# 30ApowerDist.net
KiCad netlist of a schematic drawn in EAGLE
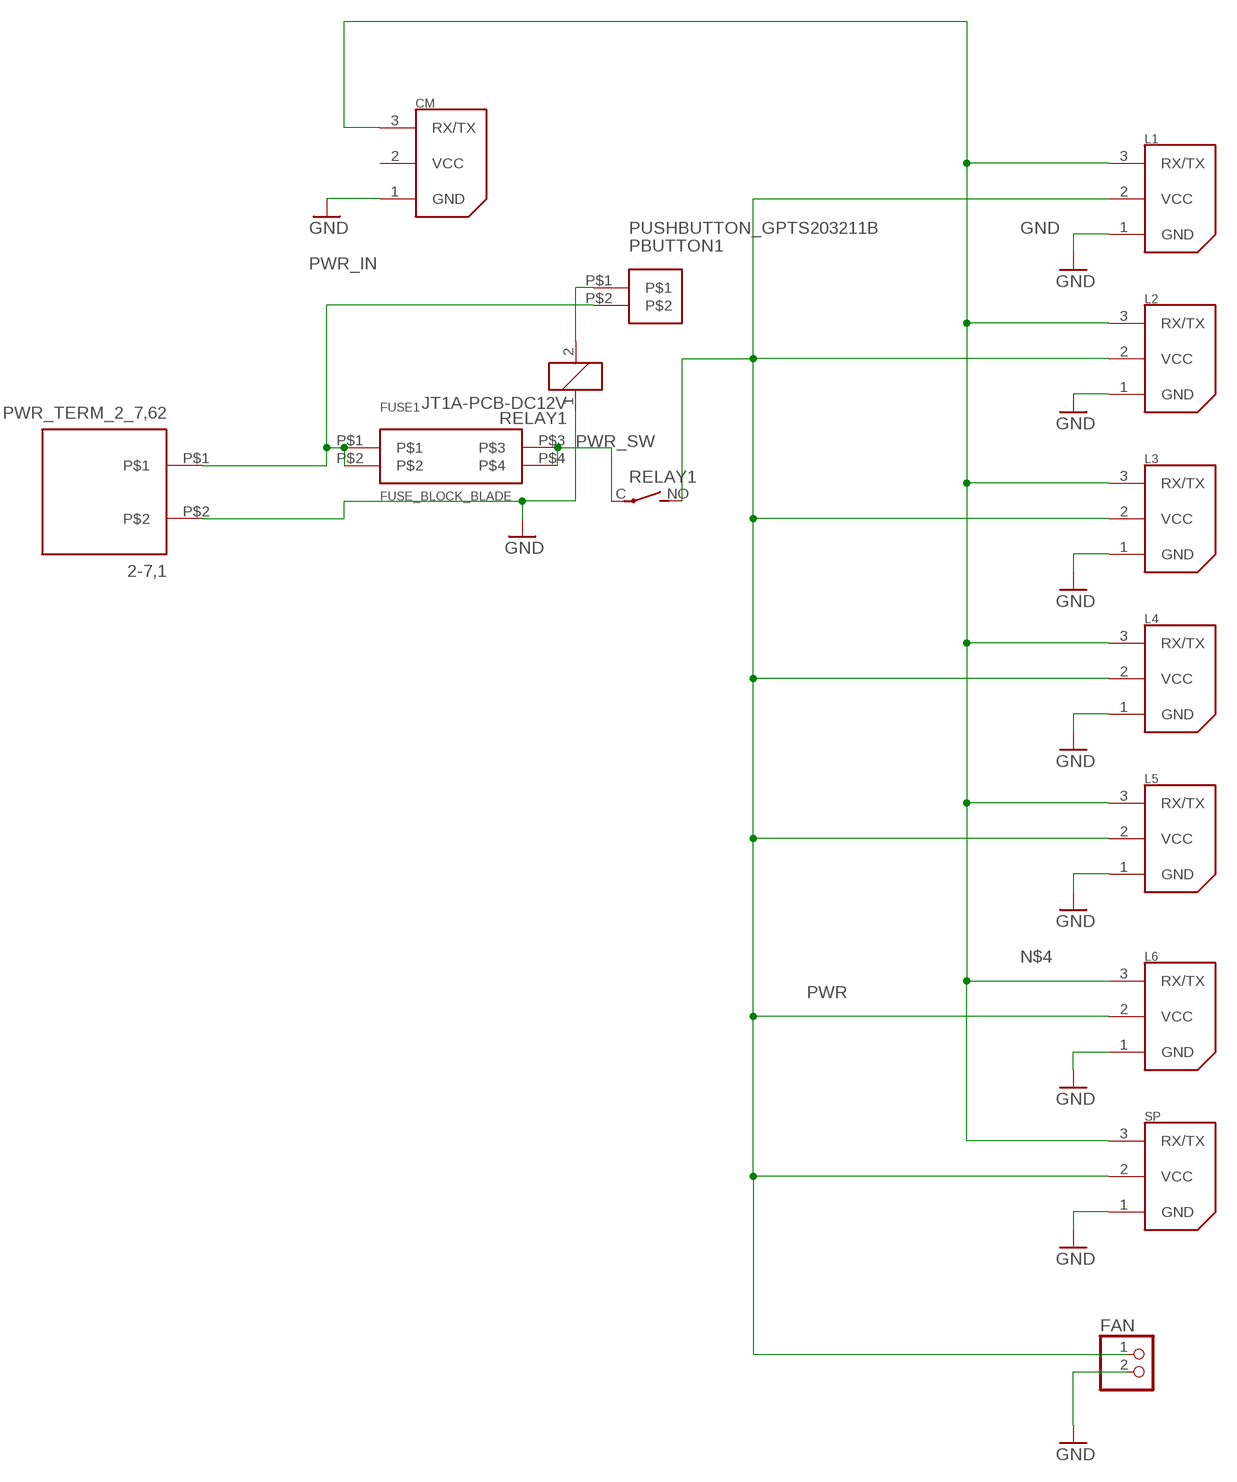
[diagram p0: schematic, sheet 1]

(export (version "E")
  (design (tool "Eeschema 10.0.6"))
  (components
    (comp (ref "2-7,1")
      (value "PWR_TERM_2_7,62")
      (footprint "eagle-import:PWR_TERM_2_7,62")
      (libsource (lib "eagle-import") (part "PWR_TERM_2_7,62"))
    )
    (comp (ref "CM")
      (value "22-03-5035")
      (footprint "eagle-import:5267-3")
      (libsource (lib "eagle-import") (part "22-03-5035"))
    )
    (comp (ref "FAN")
      (value "PINHD-1X2")
      (footprint "eagle-import:1X02")
      (libsource (lib "eagle-import") (part "PINHD-1X2"))
    )
    (comp (ref "FUSE1")
      (value "FUSE_BLOCK_BLADE")
      (footprint "eagle-import:FUSE_BLOCK_BLADE")
      (libsource (lib "eagle-import") (part "FUSE_BLOCK_BLADE"))
    )
    (comp (ref "L1")
      (value "22-03-5035")
      (footprint "eagle-import:5267-3")
      (libsource (lib "eagle-import") (part "22-03-5035"))
    )
    (comp (ref "L2")
      (value "22-03-5035")
      (footprint "eagle-import:5267-3")
      (libsource (lib "eagle-import") (part "22-03-5035"))
    )
    (comp (ref "L3")
      (value "22-03-5035")
      (footprint "eagle-import:5267-3")
      (libsource (lib "eagle-import") (part "22-03-5035"))
    )
    (comp (ref "L4")
      (value "22-03-5035")
      (footprint "eagle-import:5267-3")
      (libsource (lib "eagle-import") (part "22-03-5035"))
    )
    (comp (ref "L5")
      (value "22-03-5035")
      (footprint "eagle-import:5267-3")
      (libsource (lib "eagle-import") (part "22-03-5035"))
    )
    (comp (ref "L6")
      (value "22-03-5035")
      (footprint "eagle-import:5267-3")
      (libsource (lib "eagle-import") (part "22-03-5035"))
    )
    (comp (ref "PBUTTON1")
      (value "PUSHBUTTON_GPTS203211B")
      (footprint "eagle-import:PUSHBUTTON_GPTS203211B")
      (libsource (lib "eagle-import") (part "PUSHBUTTON_GPTS203211B"))
    )
    (comp (ref "RELAY1")
      (value "JT1A-PCB-DC12V")
      (footprint "eagle-import:JT1A-PCB")
      (libsource (lib "eagle-import") (part "JT1A?--PCBDC12V"))
    )
    (comp (ref "SP")
      (value "22-03-5035")
      (footprint "eagle-import:5267-3")
      (libsource (lib "eagle-import") (part "22-03-5035"))
    )
  )
  (nets
    (net (code "1") (name "/N$4") (class "Default")
      (node (ref "CM") (pin "3") (pinfunction "RX/TX_3") (pintype "bidirectional"))
      (node (ref "L1") (pin "3") (pinfunction "RX/TX_3") (pintype "bidirectional"))
      (node (ref "L2") (pin "3") (pinfunction "RX/TX_3") (pintype "bidirectional"))
      (node (ref "L3") (pin "3") (pinfunction "RX/TX_3") (pintype "bidirectional"))
      (node (ref "L4") (pin "3") (pinfunction "RX/TX_3") (pintype "bidirectional"))
      (node (ref "L5") (pin "3") (pinfunction "RX/TX_3") (pintype "bidirectional"))
      (node (ref "L6") (pin "3") (pinfunction "RX/TX_3") (pintype "bidirectional"))
      (node (ref "SP") (pin "3") (pinfunction "RX/TX_3") (pintype "bidirectional"))
    )
    (net (code "2") (name "/PWR") (class "Default")
      (node (ref "FAN") (pin "1") (pinfunction "1_1") (pintype "passive"))
      (node (ref "L1") (pin "2") (pinfunction "VCC_2") (pintype "bidirectional"))
      (node (ref "L2") (pin "2") (pinfunction "VCC_2") (pintype "bidirectional"))
      (node (ref "L3") (pin "2") (pinfunction "VCC_2") (pintype "bidirectional"))
      (node (ref "L4") (pin "2") (pinfunction "VCC_2") (pintype "bidirectional"))
      (node (ref "L5") (pin "2") (pinfunction "VCC_2") (pintype "bidirectional"))
      (node (ref "L6") (pin "2") (pinfunction "VCC_2") (pintype "bidirectional"))
      (node (ref "RELAY1") (pin "NO") (pinfunction "S_NO") (pintype "passive"))
      (node (ref "SP") (pin "2") (pinfunction "VCC_2") (pintype "bidirectional"))
    )
    (net (code "3") (name "/PWR_IN") (class "Default")
      (node (ref "2-7,1") (pin "P$1") (pinfunction "P$1_P$1") (pintype "bidirectional"))
      (node (ref "FUSE1") (pin "P$1") (pinfunction "P$1_P$1") (pintype "bidirectional"))
      (node (ref "FUSE1") (pin "P$2") (pinfunction "P$2_P$2") (pintype "bidirectional"))
      (node (ref "PBUTTON1") (pin "P$2") (pinfunction "P$2_P$2") (pintype "bidirectional"))
    )
    (net (code "4") (name "/PWR_SW") (class "Default")
      (node (ref "FUSE1") (pin "P$3") (pinfunction "P$3_P$3") (pintype "bidirectional"))
      (node (ref "FUSE1") (pin "P$4") (pinfunction "P$4_P$4") (pintype "bidirectional"))
      (node (ref "RELAY1") (pin "C") (pinfunction "P_C") (pintype "passive"))
    )
    (net (code "5") (name "GND") (class "Default")
      (node (ref "2-7,1") (pin "P$2") (pinfunction "P$2_P$2") (pintype "bidirectional"))
      (node (ref "CM") (pin "1") (pinfunction "GND_1") (pintype "bidirectional"))
      (node (ref "FAN") (pin "2") (pinfunction "2_2") (pintype "passive"))
      (node (ref "L1") (pin "1") (pinfunction "GND_1") (pintype "bidirectional"))
      (node (ref "L2") (pin "1") (pinfunction "GND_1") (pintype "bidirectional"))
      (node (ref "L3") (pin "1") (pinfunction "GND_1") (pintype "bidirectional"))
      (node (ref "L4") (pin "1") (pinfunction "GND_1") (pintype "bidirectional"))
      (node (ref "L5") (pin "1") (pinfunction "GND_1") (pintype "bidirectional"))
      (node (ref "L6") (pin "1") (pinfunction "GND_1") (pintype "bidirectional"))
      (node (ref "RELAY1") (pin "1") (pinfunction "1_1") (pintype "passive"))
      (node (ref "SP") (pin "1") (pinfunction "GND_1") (pintype "bidirectional"))
    )
    (net (code "6") (name "Net-(PBUTTON1-PadP$1)") (class "Default")
      (node (ref "PBUTTON1") (pin "P$1") (pinfunction "P$1_P$1") (pintype "bidirectional"))
      (node (ref "RELAY1") (pin "2") (pinfunction "2_2") (pintype "passive"))
    )
    (net (code "7") (name "unconnected-(CM-VCC-Pad2)") (class "Default")
      (node (ref "CM") (pin "2") (pinfunction "VCC_2") (pintype "bidirectional"))
    )
  )
)
